# SolarMonitorDisplayBoard.net
KiCad netlist of a schematic drawn in EAGLE
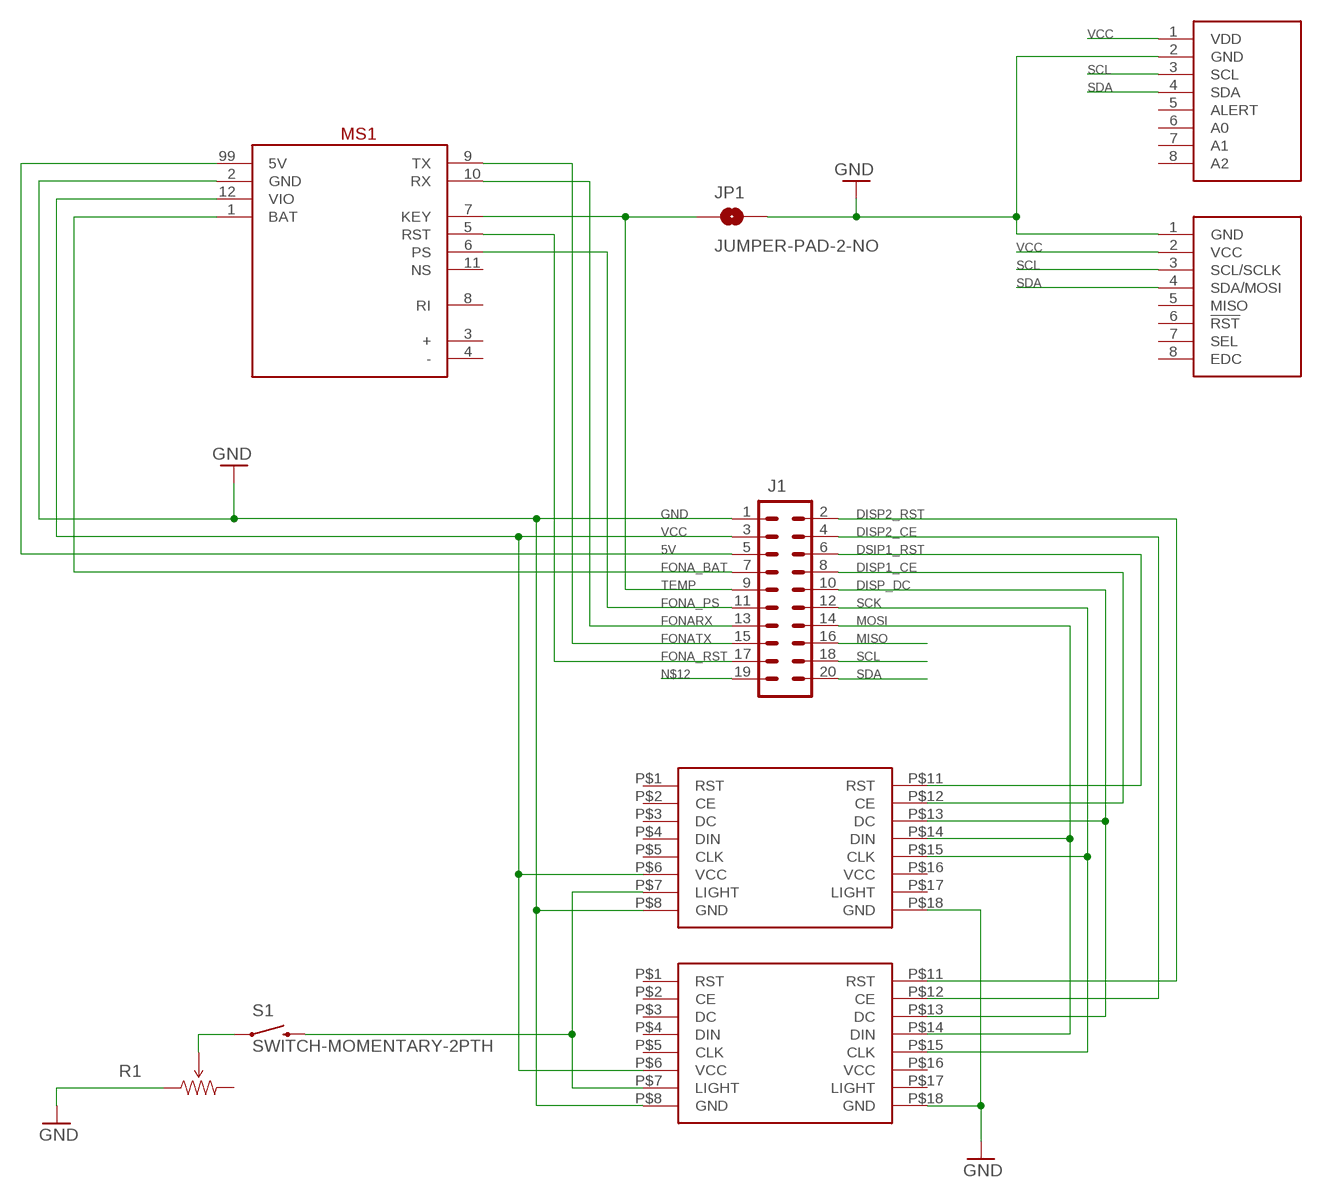
[diagram p0: schematic, sheet 1]

(export (version "E")
  (design (tool "Eeschema 10.0.6"))
  (components
    (comp (ref "BARO")
      (value "T5403_BREAKOUT")
      (footprint "eagle-import:T5403_BREAKOUT")
      (libsource (lib "eagle-import") (part "T5403_BREAKOUT"))
    )
    (comp (ref "J1")
      (value "M10X2")
      (footprint "eagle-import:2X10")
      (libsource (lib "eagle-import") (part "M10X2"))
    )
    (comp (ref "JP1")
      (value "JUMPER-PAD-2-NO")
      (footprint "eagle-import:PAD-JUMPER-2-NO_NO_SILK")
      (libsource (lib "eagle-import") (part "JUMPER-PAD-2-NO"))
    )
    (comp (ref "MS1")
      (value "FONA")
      (footprint "eagle-import:FONA")
      (libsource (lib "eagle-import") (part "FONA"))
    )
    (comp (ref "R1")
      (value "TRIMPOTPTH")
      (footprint "eagle-import:TRIM_POT_PTH")
      (libsource (lib "eagle-import") (part "TRIMPOTPTH"))
    )
    (comp (ref "S1")
      (value "SWITCH-MOMENTARY-2PTH")
      (footprint "eagle-import:TACTILE-PTH")
      (libsource (lib "eagle-import") (part "SWITCH-MOMENTARY-2PTH"))
    )
    (comp (ref "TEMP")
      (value "MCP9808_BREAKOUT")
      (footprint "eagle-import:MCP9808_BREAKOUT")
      (libsource (lib "eagle-import") (part "MCP9808_BREAKOUT"))
    )
    (comp (ref "U$1")
      (value "NOKIA_LCD_BREAKOUT")
      (footprint "eagle-import:NOKIA_LCD_BREAKOUT")
      (libsource (lib "eagle-import") (part "NOKIA_LCD_BREAKOUT"))
    )
    (comp (ref "U$2")
      (value "NOKIA_LCD_BREAKOUT")
      (footprint "eagle-import:NOKIA_LCD_BREAKOUT")
      (libsource (lib "eagle-import") (part "NOKIA_LCD_BREAKOUT"))
    )
  )
  (nets
    (net (code "1") (name "/5V") (class "Default")
      (node (ref "J1") (pin "5") (pinfunction "5_5") (pintype "passive"))
      (node (ref "MS1") (pin "99") (pinfunction "5V_99") (pintype "bidirectional"))
    )
    (net (code "2") (name "/DISP1_CE") (class "Default")
      (node (ref "J1") (pin "8") (pinfunction "8_8") (pintype "passive"))
      (node (ref "U$2") (pin "P$12") (pinfunction "CE_P$12") (pintype "bidirectional"))
    )
    (net (code "3") (name "/DISP2_CE") (class "Default")
      (node (ref "J1") (pin "4") (pinfunction "4_4") (pintype "passive"))
      (node (ref "U$1") (pin "P$12") (pinfunction "CE_P$12") (pintype "bidirectional"))
    )
    (net (code "4") (name "/DISP2_RST") (class "Default")
      (node (ref "J1") (pin "2") (pinfunction "2_2") (pintype "passive"))
      (node (ref "U$1") (pin "P$11") (pinfunction "RST_P$11") (pintype "bidirectional"))
    )
    (net (code "5") (name "/DISP_DC") (class "Default")
      (node (ref "J1") (pin "10") (pinfunction "10_10") (pintype "passive"))
      (node (ref "U$1") (pin "P$13") (pinfunction "DC_P$13") (pintype "bidirectional"))
      (node (ref "U$2") (pin "P$13") (pinfunction "DC_P$13") (pintype "bidirectional"))
    )
    (net (code "6") (name "/DSIP1_RST") (class "Default")
      (node (ref "J1") (pin "6") (pinfunction "6_6") (pintype "passive"))
      (node (ref "U$2") (pin "P$11") (pinfunction "RST_P$11") (pintype "bidirectional"))
    )
    (net (code "7") (name "/FONARX") (class "Default")
      (node (ref "J1") (pin "13") (pinfunction "13_13") (pintype "passive"))
      (node (ref "MS1") (pin "10") (pinfunction "RX_10") (pintype "bidirectional"))
    )
    (net (code "8") (name "/FONATX") (class "Default")
      (node (ref "J1") (pin "15") (pinfunction "15_15") (pintype "passive"))
      (node (ref "MS1") (pin "9") (pinfunction "TX_9") (pintype "bidirectional"))
    )
    (net (code "9") (name "/FONA_BAT") (class "Default")
      (node (ref "J1") (pin "7") (pinfunction "7_7") (pintype "passive"))
      (node (ref "MS1") (pin "1") (pinfunction "BAT_1") (pintype "bidirectional"))
    )
    (net (code "10") (name "/FONA_PS") (class "Default")
      (node (ref "J1") (pin "11") (pinfunction "11_11") (pintype "passive"))
      (node (ref "MS1") (pin "6") (pinfunction "PS_6") (pintype "bidirectional"))
    )
    (net (code "11") (name "/FONA_RST") (class "Default")
      (node (ref "J1") (pin "17") (pinfunction "17_17") (pintype "passive"))
      (node (ref "MS1") (pin "5") (pinfunction "RST_5") (pintype "bidirectional"))
    )
    (net (code "12") (name "/MISO") (class "Default")
      (node (ref "J1") (pin "16") (pinfunction "16_16") (pintype "passive"))
    )
    (net (code "13") (name "/MOSI") (class "Default")
      (node (ref "J1") (pin "14") (pinfunction "14_14") (pintype "passive"))
      (node (ref "U$1") (pin "P$14") (pinfunction "DIN_P$14") (pintype "bidirectional"))
      (node (ref "U$2") (pin "P$14") (pinfunction "DIN_P$14") (pintype "bidirectional"))
    )
    (net (code "14") (name "/N$12") (class "Default")
      (node (ref "J1") (pin "19") (pinfunction "19_19") (pintype "passive"))
    )
    (net (code "15") (name "/SCK") (class "Default")
      (node (ref "J1") (pin "12") (pinfunction "12_12") (pintype "passive"))
      (node (ref "U$1") (pin "P$15") (pinfunction "CLK_P$15") (pintype "bidirectional"))
      (node (ref "U$2") (pin "P$15") (pinfunction "CLK_P$15") (pintype "bidirectional"))
    )
    (net (code "16") (name "/SCL") (class "Default")
      (node (ref "BARO") (pin "3") (pinfunction "SCL/SCLK_3") (pintype "bidirectional"))
      (node (ref "J1") (pin "18") (pinfunction "18_18") (pintype "passive"))
      (node (ref "TEMP") (pin "3") (pinfunction "SCL_3") (pintype "bidirectional"))
    )
    (net (code "17") (name "/SDA") (class "Default")
      (node (ref "BARO") (pin "4") (pinfunction "SDA/MOSI_4") (pintype "bidirectional"))
      (node (ref "J1") (pin "20") (pinfunction "20_20") (pintype "passive"))
      (node (ref "TEMP") (pin "4") (pinfunction "SDA_4") (pintype "bidirectional"))
    )
    (net (code "18") (name "/TEMP") (class "Default")
      (node (ref "J1") (pin "9") (pinfunction "9_9") (pintype "passive"))
      (node (ref "JP1") (pin "1") (pinfunction "1_1") (pintype "passive"))
      (node (ref "MS1") (pin "7") (pinfunction "KEY_7") (pintype "bidirectional"))
    )
    (net (code "19") (name "/VCC") (class "Default")
      (node (ref "BARO") (pin "2") (pinfunction "VCC_2") (pintype "bidirectional"))
      (node (ref "J1") (pin "3") (pinfunction "3_3") (pintype "passive"))
      (node (ref "MS1") (pin "12") (pinfunction "VIO_12") (pintype "bidirectional"))
      (node (ref "TEMP") (pin "1") (pinfunction "VDD_1") (pintype "bidirectional"))
      (node (ref "U$1") (pin "P$6") (pinfunction "VCC_P$6") (pintype "bidirectional"))
      (node (ref "U$2") (pin "P$6") (pinfunction "VCC_P$6") (pintype "bidirectional"))
    )
    (net (code "20") (name "GND") (class "Default")
      (node (ref "BARO") (pin "1") (pinfunction "GND_1") (pintype "bidirectional"))
      (node (ref "J1") (pin "1") (pinfunction "1_1") (pintype "passive"))
      (node (ref "JP1") (pin "2") (pinfunction "2_2") (pintype "passive"))
      (node (ref "MS1") (pin "2") (pinfunction "GND_2") (pintype "bidirectional"))
      (node (ref "R1") (pin "1") (pinfunction "CCW_1") (pintype "passive"))
      (node (ref "TEMP") (pin "2") (pinfunction "GND_2") (pintype "bidirectional"))
      (node (ref "U$1") (pin "P$18") (pinfunction "GND_P$18") (pintype "bidirectional"))
      (node (ref "U$1") (pin "P$8") (pinfunction "GND_P$8") (pintype "bidirectional"))
      (node (ref "U$2") (pin "P$18") (pinfunction "GND_P$18") (pintype "bidirectional"))
      (node (ref "U$2") (pin "P$8") (pinfunction "GND_P$8") (pintype "bidirectional"))
    )
    (net (code "21") (name "Net-(R1-WIPER)") (class "Default")
      (node (ref "R1") (pin "2") (pinfunction "WIPER_2") (pintype "passive"))
      (node (ref "S1") (pin "1") (pinfunction "1_1") (pintype "passive"))
    )
    (net (code "22") (name "Net-(S1-2)") (class "Default")
      (node (ref "S1") (pin "3") (pinfunction "2_3") (pintype "passive"))
      (node (ref "U$1") (pin "P$7") (pinfunction "LIGHT_P$7") (pintype "bidirectional"))
      (node (ref "U$2") (pin "P$7") (pinfunction "LIGHT_P$7") (pintype "bidirectional"))
    )
    (net (code "23") (name "unconnected-(BARO-EDC-Pad8)") (class "Default")
      (node (ref "BARO") (pin "8") (pinfunction "EDC_8") (pintype "bidirectional"))
    )
    (net (code "24") (name "unconnected-(BARO-MISO-Pad5)") (class "Default")
      (node (ref "BARO") (pin "5") (pinfunction "MISO_5") (pintype "bidirectional"))
    )
    (net (code "25") (name "unconnected-(BARO-SEL-Pad7)") (class "Default")
      (node (ref "BARO") (pin "7") (pinfunction "SEL_7") (pintype "bidirectional"))
    )
    (net (code "26") (name "unconnected-(BARO-~{RST}-Pad6)") (class "Default")
      (node (ref "BARO") (pin "6") (pinfunction "~{RST}_6") (pintype "bidirectional"))
    )
    (net (code "27") (name "unconnected-(MS1-+-Pad3)") (class "Default")
      (node (ref "MS1") (pin "3") (pinfunction "+_3") (pintype "bidirectional"))
    )
    (net (code "28") (name "unconnected-(MS1---Pad4)") (class "Default")
      (node (ref "MS1") (pin "4") (pinfunction "-_4") (pintype "bidirectional"))
    )
    (net (code "29") (name "unconnected-(MS1-NS-Pad11)") (class "Default")
      (node (ref "MS1") (pin "11") (pinfunction "NS_11") (pintype "bidirectional"))
    )
    (net (code "30") (name "unconnected-(MS1-RI-Pad8)") (class "Default")
      (node (ref "MS1") (pin "8") (pinfunction "RI_8") (pintype "bidirectional"))
    )
    (net (code "31") (name "unconnected-(R1-CW-Pad3)") (class "Default")
      (node (ref "R1") (pin "3") (pinfunction "CW_3") (pintype "passive"))
    )
    (net (code "32") (name "unconnected-(TEMP-A0-Pad6)") (class "Default")
      (node (ref "TEMP") (pin "6") (pinfunction "A0_6") (pintype "bidirectional"))
    )
    (net (code "33") (name "unconnected-(TEMP-A1-Pad7)") (class "Default")
      (node (ref "TEMP") (pin "7") (pinfunction "A1_7") (pintype "bidirectional"))
    )
    (net (code "34") (name "unconnected-(TEMP-A2-Pad8)") (class "Default")
      (node (ref "TEMP") (pin "8") (pinfunction "A2_8") (pintype "bidirectional"))
    )
    (net (code "35") (name "unconnected-(TEMP-ALERT-Pad5)") (class "Default")
      (node (ref "TEMP") (pin "5") (pinfunction "ALERT_5") (pintype "bidirectional"))
    )
    (net (code "36") (name "unconnected-(U$1-CE-PadP$2)") (class "Default")
      (node (ref "U$1") (pin "P$2") (pinfunction "CE_P$2") (pintype "bidirectional"))
    )
    (net (code "37") (name "unconnected-(U$1-CLK-PadP$5)") (class "Default")
      (node (ref "U$1") (pin "P$5") (pinfunction "CLK_P$5") (pintype "bidirectional"))
    )
    (net (code "38") (name "unconnected-(U$1-DC-PadP$3)") (class "Default")
      (node (ref "U$1") (pin "P$3") (pinfunction "DC_P$3") (pintype "bidirectional"))
    )
    (net (code "39") (name "unconnected-(U$1-DIN-PadP$4)") (class "Default")
      (node (ref "U$1") (pin "P$4") (pinfunction "DIN_P$4") (pintype "bidirectional"))
    )
    (net (code "40") (name "unconnected-(U$1-LIGHT-PadP$17)") (class "Default")
      (node (ref "U$1") (pin "P$17") (pinfunction "LIGHT_P$17") (pintype "bidirectional"))
    )
    (net (code "41") (name "unconnected-(U$1-RST-PadP$1)") (class "Default")
      (node (ref "U$1") (pin "P$1") (pinfunction "RST_P$1") (pintype "bidirectional"))
    )
    (net (code "42") (name "unconnected-(U$1-VCC-PadP$16)") (class "Default")
      (node (ref "U$1") (pin "P$16") (pinfunction "VCC_P$16") (pintype "bidirectional"))
    )
    (net (code "43") (name "unconnected-(U$2-CE-PadP$2)") (class "Default")
      (node (ref "U$2") (pin "P$2") (pinfunction "CE_P$2") (pintype "bidirectional"))
    )
    (net (code "44") (name "unconnected-(U$2-CLK-PadP$5)") (class "Default")
      (node (ref "U$2") (pin "P$5") (pinfunction "CLK_P$5") (pintype "bidirectional"))
    )
    (net (code "45") (name "unconnected-(U$2-DC-PadP$3)") (class "Default")
      (node (ref "U$2") (pin "P$3") (pinfunction "DC_P$3") (pintype "bidirectional"))
    )
    (net (code "46") (name "unconnected-(U$2-DIN-PadP$4)") (class "Default")
      (node (ref "U$2") (pin "P$4") (pinfunction "DIN_P$4") (pintype "bidirectional"))
    )
    (net (code "47") (name "unconnected-(U$2-LIGHT-PadP$17)") (class "Default")
      (node (ref "U$2") (pin "P$17") (pinfunction "LIGHT_P$17") (pintype "bidirectional"))
    )
    (net (code "48") (name "unconnected-(U$2-RST-PadP$1)") (class "Default")
      (node (ref "U$2") (pin "P$1") (pinfunction "RST_P$1") (pintype "bidirectional"))
    )
    (net (code "49") (name "unconnected-(U$2-VCC-PadP$16)") (class "Default")
      (node (ref "U$2") (pin "P$16") (pinfunction "VCC_P$16") (pintype "bidirectional"))
    )
  )
)
